# harp_timestamp_generator_gen1.net
KiCad netlist of a schematic drawn in EAGLE
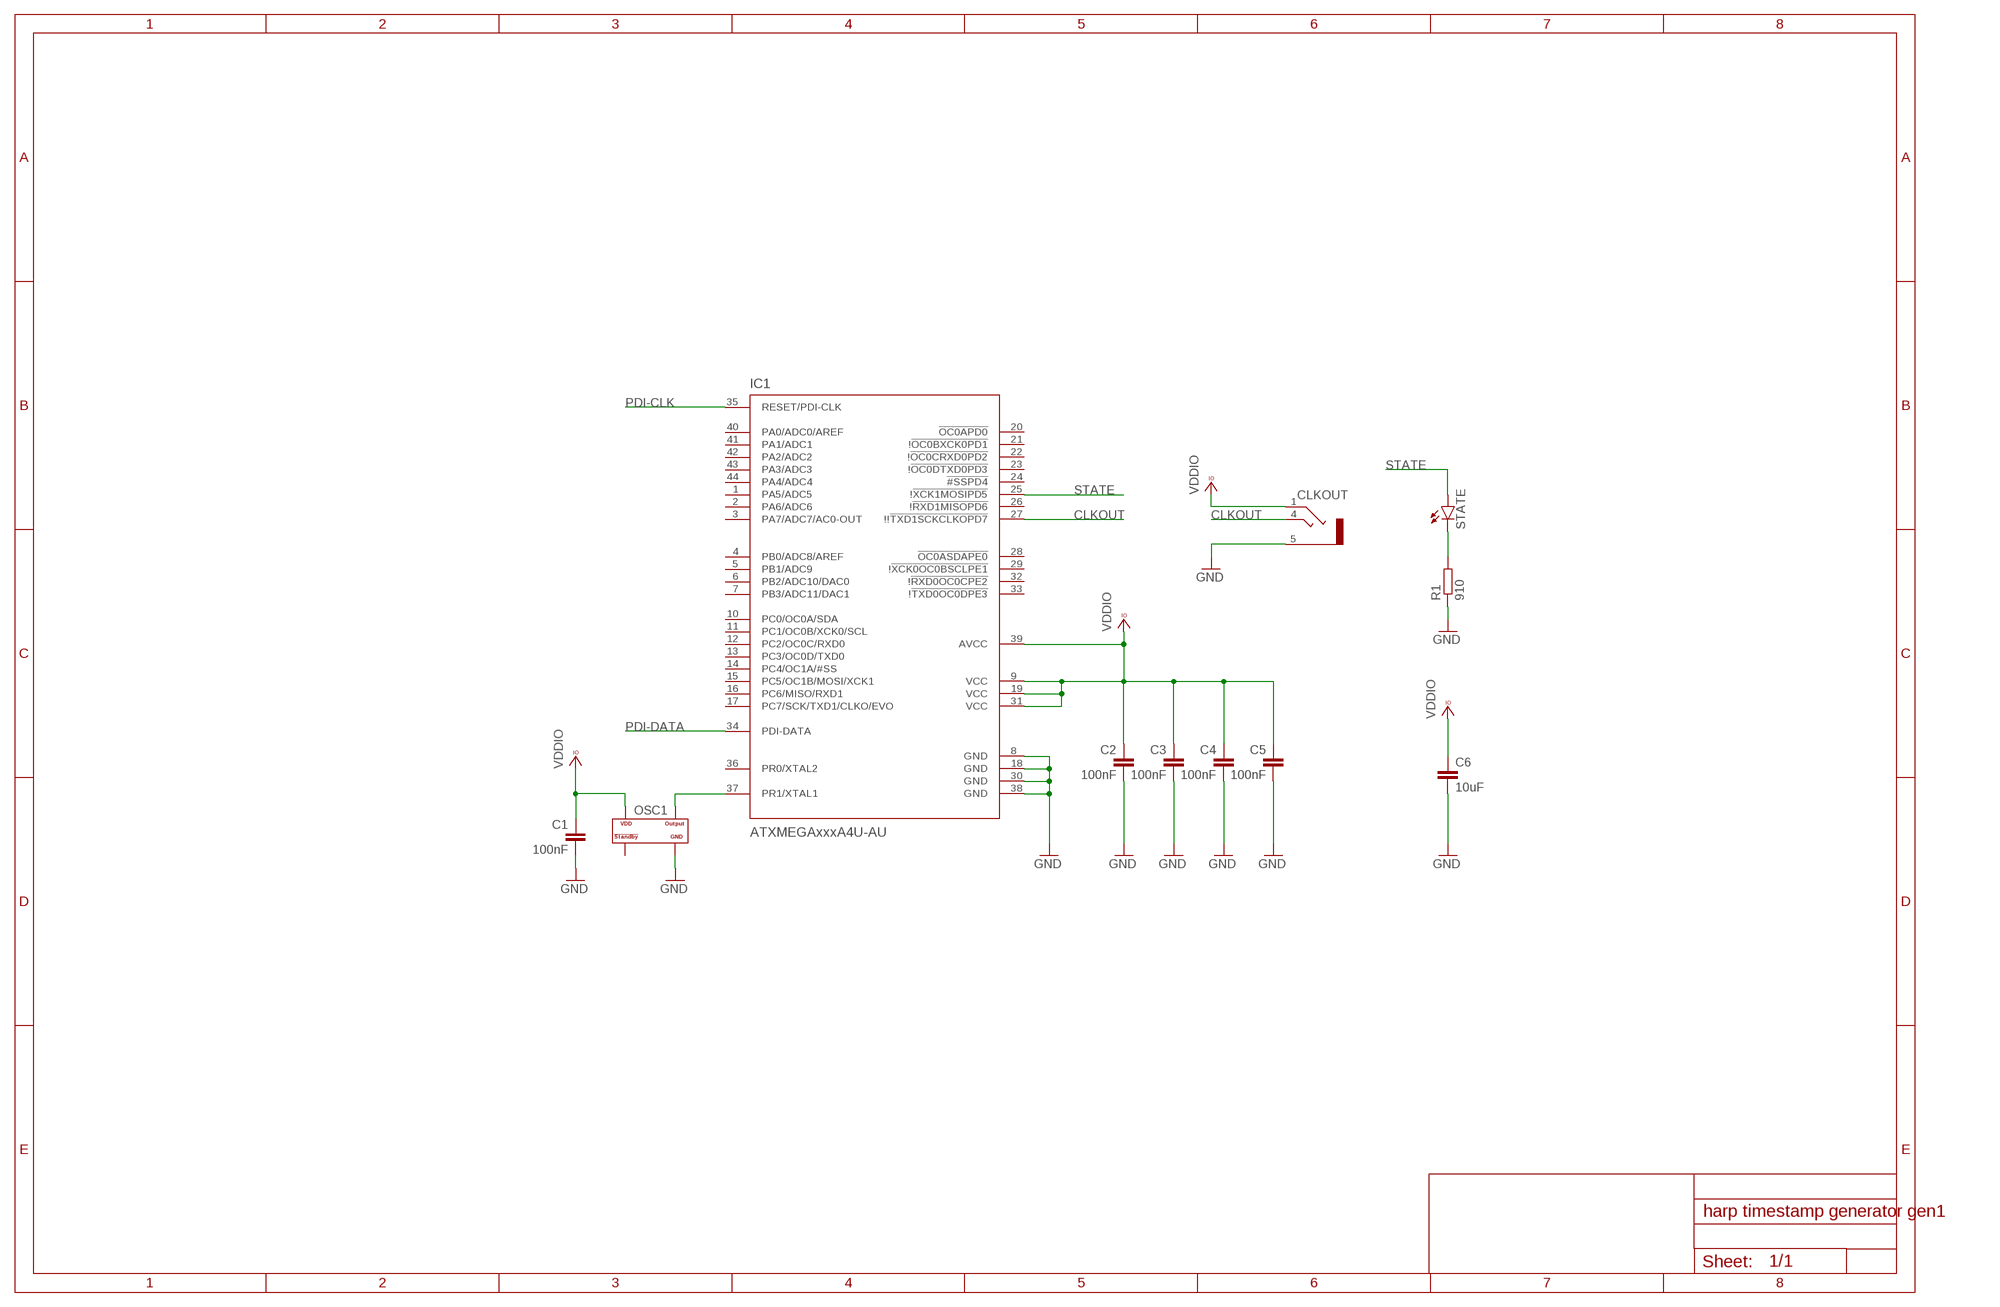
[diagram p0: schematic, sheet 1]

(export (version "E")
  (design (tool "Eeschema 10.0.6"))
  (components
    (comp (ref "C1")
      (value "100nF")
      (footprint "eagle-import:C0402")
      (libsource (lib "eagle-import") (part "C-EUC0402"))
    )
    (comp (ref "C2")
      (value "100nF")
      (footprint "eagle-import:C0402")
      (libsource (lib "eagle-import") (part "C-EUC0402"))
    )
    (comp (ref "C3")
      (value "100nF")
      (footprint "eagle-import:C0402")
      (libsource (lib "eagle-import") (part "C-EUC0402"))
    )
    (comp (ref "C4")
      (value "100nF")
      (footprint "eagle-import:C0402")
      (libsource (lib "eagle-import") (part "C-EUC0402"))
    )
    (comp (ref "C5")
      (value "100nF")
      (footprint "eagle-import:C0402")
      (libsource (lib "eagle-import") (part "C-EUC0402"))
    )
    (comp (ref "C6")
      (value "10uF")
      (footprint "eagle-import:C0603")
      (libsource (lib "eagle-import") (part "C-EUC0603"))
    )
    (comp (ref "CLKOUT")
      (value "STEREO_JACK")
      (footprint "eagle-import:35RASMT2BHNTRX")
      (libsource (lib "eagle-import") (part "STEREO_JACK"))
    )
    (comp (ref "IC1")
      (value "ATXMEGAxxxA4U-AU")
      (footprint "eagle-import:QFP80P1200X1200X120-44N")
      (libsource (lib "eagle-import") (part "AT-XMEGA-XXA4-AU"))
    )
    (comp (ref "OSC1")
      (value "CNP-MISCELLANEOUS_OSCILLATOR")
      (footprint "eagle-import:CNP-MISCELLANEOUS_OSCILLATOR_3.2X2.5")
      (libsource (lib "eagle-import") (part "CNP-MISCELLANEOUS_OSCILLATOR"))
    )
    (comp (ref "R1")
      (value "910")
      (footprint "eagle-import:R0402")
      (libsource (lib "eagle-import") (part "R-EU_R0402"))
    )
    (comp (ref "STATE")
      (value "LEDCHIP-LED0603")
      (footprint "eagle-import:CHIP-LED0603")
      (libsource (lib "eagle-import") (part "LEDCHIP-LED0603"))
    )
  )
  (nets
    (net (code "1") (name "/CLKOUT") (class "Default")
      (node (ref "CLKOUT") (pin "4") (pinfunction "4_4") (pintype "passive"))
      (node (ref "IC1") (pin "27") (pinfunction "~~{TXD1SCKCLKOPD7}_27") (pintype "bidirectional"))
    )
    (net (code "2") (name "/PDI-CLK") (class "Default")
      (node (ref "IC1") (pin "35") (pinfunction "RESET/PDI-CLK_35") (pintype "input"))
    )
    (net (code "3") (name "/PDI-DATA") (class "Default")
      (node (ref "IC1") (pin "34") (pinfunction "PDI-DATA_34") (pintype "bidirectional"))
    )
    (net (code "4") (name "/STATE") (class "Default")
      (node (ref "IC1") (pin "25") (pinfunction "~XCK1MOSIPD5_25") (pintype "bidirectional"))
      (node (ref "STATE") (pin "A") (pinfunction "A_A") (pintype "passive"))
    )
    (net (code "5") (name "GND") (class "Default")
      (node (ref "C1") (pin "2") (pinfunction "2_2") (pintype "passive"))
      (node (ref "C2") (pin "2") (pinfunction "2_2") (pintype "passive"))
      (node (ref "C3") (pin "2") (pinfunction "2_2") (pintype "passive"))
      (node (ref "C4") (pin "2") (pinfunction "2_2") (pintype "passive"))
      (node (ref "C5") (pin "2") (pinfunction "2_2") (pintype "passive"))
      (node (ref "C6") (pin "2") (pinfunction "2_2") (pintype "passive"))
      (node (ref "CLKOUT") (pin "5") (pinfunction "5_5") (pintype "passive"))
      (node (ref "IC1") (pin "18") (pinfunction "GND_18") (pintype "power_in"))
      (node (ref "IC1") (pin "30") (pinfunction "GND_30") (pintype "power_in"))
      (node (ref "IC1") (pin "38") (pinfunction "GND_38") (pintype "power_in"))
      (node (ref "IC1") (pin "8") (pinfunction "GND_8") (pintype "power_in"))
      (node (ref "OSC1") (pin "P$2") (pinfunction "GND_P$2") (pintype "passive"))
      (node (ref "R1") (pin "1") (pinfunction "1_1") (pintype "passive"))
    )
    (net (code "6") (name "Net-(IC1-PR1{slash}XTAL1)") (class "Default")
      (node (ref "IC1") (pin "37") (pinfunction "PR1/XTAL1_37") (pintype "bidirectional"))
      (node (ref "OSC1") (pin "P$3") (pinfunction "OUTPUT_P$3") (pintype "passive"))
    )
    (net (code "7") (name "Net-(R1-Pad2)") (class "Default")
      (node (ref "R1") (pin "2") (pinfunction "2_2") (pintype "passive"))
      (node (ref "STATE") (pin "C") (pinfunction "C_C") (pintype "passive"))
    )
    (net (code "8") (name "VDDIO") (class "Default")
      (node (ref "C1") (pin "1") (pinfunction "1_1") (pintype "passive"))
      (node (ref "C2") (pin "1") (pinfunction "1_1") (pintype "passive"))
      (node (ref "C3") (pin "1") (pinfunction "1_1") (pintype "passive"))
      (node (ref "C4") (pin "1") (pinfunction "1_1") (pintype "passive"))
      (node (ref "C5") (pin "1") (pinfunction "1_1") (pintype "passive"))
      (node (ref "C6") (pin "1") (pinfunction "1_1") (pintype "passive"))
      (node (ref "CLKOUT") (pin "1") (pinfunction "1_1") (pintype "passive"))
      (node (ref "IC1") (pin "19") (pinfunction "VCC_19") (pintype "power_in"))
      (node (ref "IC1") (pin "31") (pinfunction "VCC_31") (pintype "power_in"))
      (node (ref "IC1") (pin "39") (pinfunction "AVCC_39") (pintype "power_in"))
      (node (ref "IC1") (pin "9") (pinfunction "VCC_9") (pintype "power_in"))
      (node (ref "OSC1") (pin "P$4") (pinfunction "VDD_P$4") (pintype "passive"))
    )
    (net (code "9") (name "unconnected-(IC1-PA0{slash}ADC0{slash}AREF-Pad40)") (class "Default")
      (node (ref "IC1") (pin "40") (pinfunction "PA0/ADC0/AREF_40") (pintype "bidirectional"))
    )
    (net (code "10") (name "unconnected-(IC1-PA1{slash}ADC1-Pad41)") (class "Default")
      (node (ref "IC1") (pin "41") (pinfunction "PA1/ADC1_41") (pintype "bidirectional"))
    )
    (net (code "11") (name "unconnected-(IC1-PA2{slash}ADC2-Pad42)") (class "Default")
      (node (ref "IC1") (pin "42") (pinfunction "PA2/ADC2_42") (pintype "bidirectional"))
    )
    (net (code "12") (name "unconnected-(IC1-PA3{slash}ADC3-Pad43)") (class "Default")
      (node (ref "IC1") (pin "43") (pinfunction "PA3/ADC3_43") (pintype "bidirectional"))
    )
    (net (code "13") (name "unconnected-(IC1-PA4{slash}ADC4-Pad44)") (class "Default")
      (node (ref "IC1") (pin "44") (pinfunction "PA4/ADC4_44") (pintype "bidirectional"))
    )
    (net (code "14") (name "unconnected-(IC1-PA5{slash}ADC5-Pad1)") (class "Default")
      (node (ref "IC1") (pin "1") (pinfunction "PA5/ADC5_1") (pintype "bidirectional"))
    )
    (net (code "15") (name "unconnected-(IC1-PA6{slash}ADC6-Pad2)") (class "Default")
      (node (ref "IC1") (pin "2") (pinfunction "PA6/ADC6_2") (pintype "bidirectional"))
    )
    (net (code "16") (name "unconnected-(IC1-PA7{slash}ADC7{slash}AC0-OUT-Pad3)") (class "Default")
      (node (ref "IC1") (pin "3") (pinfunction "PA7/ADC7/AC0-OUT_3") (pintype "bidirectional"))
    )
    (net (code "17") (name "unconnected-(IC1-PB0{slash}ADC8{slash}AREF-Pad4)") (class "Default")
      (node (ref "IC1") (pin "4") (pinfunction "PB0/ADC8/AREF_4") (pintype "bidirectional"))
    )
    (net (code "18") (name "unconnected-(IC1-PB1{slash}ADC9-Pad5)") (class "Default")
      (node (ref "IC1") (pin "5") (pinfunction "PB1/ADC9_5") (pintype "bidirectional"))
    )
    (net (code "19") (name "unconnected-(IC1-PB2{slash}ADC10{slash}DAC0-Pad6)") (class "Default")
      (node (ref "IC1") (pin "6") (pinfunction "PB2/ADC10/DAC0_6") (pintype "bidirectional"))
    )
    (net (code "20") (name "unconnected-(IC1-PB3{slash}ADC11{slash}DAC1-Pad7)") (class "Default")
      (node (ref "IC1") (pin "7") (pinfunction "PB3/ADC11/DAC1_7") (pintype "bidirectional"))
    )
    (net (code "21") (name "unconnected-(IC1-PC0{slash}OC0A{slash}SDA-Pad10)") (class "Default")
      (node (ref "IC1") (pin "10") (pinfunction "PC0/OC0A/SDA_10") (pintype "bidirectional"))
    )
    (net (code "22") (name "unconnected-(IC1-PC1{slash}OC0B{slash}XCK0{slash}SCL-Pad11)") (class "Default")
      (node (ref "IC1") (pin "11") (pinfunction "PC1/OC0B/XCK0/SCL_11") (pintype "bidirectional"))
    )
    (net (code "23") (name "unconnected-(IC1-PC2{slash}OC0C{slash}RXD0-Pad12)") (class "Default")
      (node (ref "IC1") (pin "12") (pinfunction "PC2/OC0C/RXD0_12") (pintype "bidirectional"))
    )
    (net (code "24") (name "unconnected-(IC1-PC3{slash}OC0D{slash}TXD0-Pad13)") (class "Default")
      (node (ref "IC1") (pin "13") (pinfunction "PC3/OC0D/TXD0_13") (pintype "bidirectional"))
    )
    (net (code "25") (name "unconnected-(IC1-PC4{slash}OC1A{slash}#SS-Pad14)") (class "Default")
      (node (ref "IC1") (pin "14") (pinfunction "PC4/OC1A/#SS_14") (pintype "bidirectional"))
    )
    (net (code "26") (name "unconnected-(IC1-PC5{slash}OC1B{slash}MOSI{slash}XCK1-Pad15)") (class "Default")
      (node (ref "IC1") (pin "15") (pinfunction "PC5/OC1B/MOSI/XCK1_15") (pintype "bidirectional"))
    )
    (net (code "27") (name "unconnected-(IC1-PC6{slash}MISO{slash}RXD1-Pad16)") (class "Default")
      (node (ref "IC1") (pin "16") (pinfunction "PC6/MISO/RXD1_16") (pintype "bidirectional"))
    )
    (net (code "28") (name "unconnected-(IC1-PC7{slash}SCK{slash}TXD1{slash}CLKO{slash}EVO-Pad17)") (class "Default")
      (node (ref "IC1") (pin "17") (pinfunction "PC7/SCK/TXD1/CLKO/EVO_17") (pintype "bidirectional"))
    )
    (net (code "29") (name "unconnected-(IC1-PR0{slash}XTAL2-Pad36)") (class "Default")
      (node (ref "IC1") (pin "36") (pinfunction "PR0/XTAL2_36") (pintype "bidirectional"))
    )
    (net (code "30") (name "unconnected-(IC1-~OC0BXCK0PD1-Pad21)") (class "Default")
      (node (ref "IC1") (pin "21") (pinfunction "~OC0BXCK0PD1_21") (pintype "bidirectional"))
    )
    (net (code "31") (name "unconnected-(IC1-~OC0CRXD0PD2-Pad22)") (class "Default")
      (node (ref "IC1") (pin "22") (pinfunction "~OC0CRXD0PD2_22") (pintype "bidirectional"))
    )
    (net (code "32") (name "unconnected-(IC1-~OC0DTXD0PD3-Pad23)") (class "Default")
      (node (ref "IC1") (pin "23") (pinfunction "~OC0DTXD0PD3_23") (pintype "bidirectional"))
    )
    (net (code "33") (name "unconnected-(IC1-~RXD0OC0CPE2-Pad32)") (class "Default")
      (node (ref "IC1") (pin "32") (pinfunction "~RXD0OC0CPE2_32") (pintype "bidirectional"))
    )
    (net (code "34") (name "unconnected-(IC1-~RXD1MISOPD6-Pad26)") (class "Default")
      (node (ref "IC1") (pin "26") (pinfunction "~RXD1MISOPD6_26") (pintype "bidirectional"))
    )
    (net (code "35") (name "unconnected-(IC1-~TXD0OC0DPE3-Pad33)") (class "Default")
      (node (ref "IC1") (pin "33") (pinfunction "~TXD0OC0DPE3_33") (pintype "bidirectional"))
    )
    (net (code "36") (name "unconnected-(IC1-~XCK0OC0BSCLPE1-Pad29)") (class "Default")
      (node (ref "IC1") (pin "29") (pinfunction "~XCK0OC0BSCLPE1_29") (pintype "bidirectional"))
    )
    (net (code "37") (name "unconnected-(IC1-~{#SSPD4}-Pad24)") (class "Default")
      (node (ref "IC1") (pin "24") (pinfunction "~{#SSPD4}_24") (pintype "bidirectional"))
    )
    (net (code "38") (name "unconnected-(IC1-~{OC0APD0}-Pad20)") (class "Default")
      (node (ref "IC1") (pin "20") (pinfunction "~{OC0APD0}_20") (pintype "bidirectional"))
    )
    (net (code "39") (name "unconnected-(IC1-~{OC0ASDAPE0}-Pad28)") (class "Default")
      (node (ref "IC1") (pin "28") (pinfunction "~{OC0ASDAPE0}_28") (pintype "bidirectional"))
    )
    (net (code "40") (name "unconnected-(OSC1-STANDBY#-PadP$1)") (class "Default")
      (node (ref "OSC1") (pin "P$1") (pinfunction "STANDBY#_P$1") (pintype "passive"))
    )
  )
)
